# PolIrkutska_DOZATOR_el.net
KiCad netlist of a schematic drawn in EAGLE
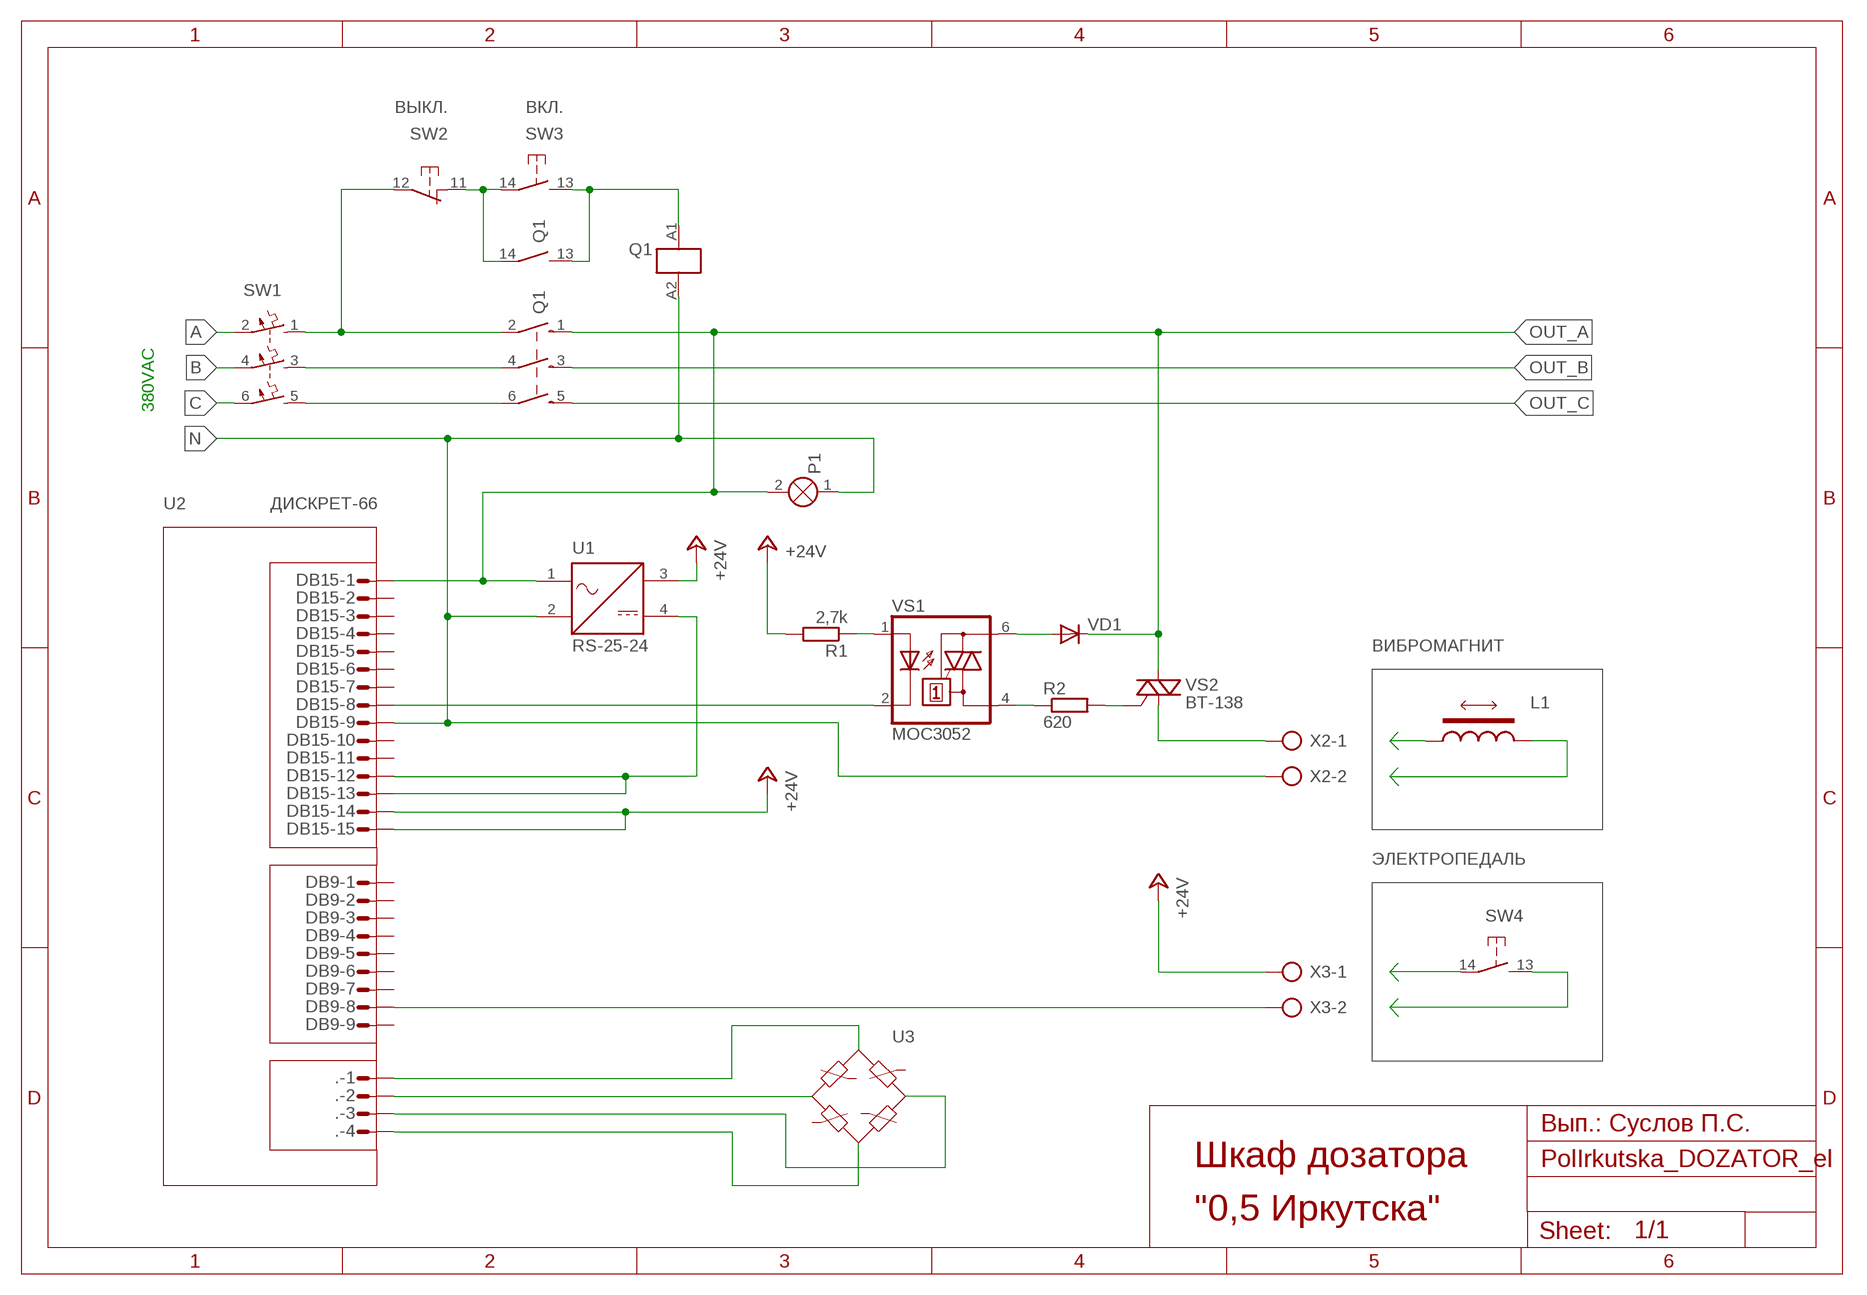
[diagram p0: schematic, sheet 1]

(export (version "E")
  (design (tool "Eeschema 10.0.6"))
  (components
    (comp (ref ".")
      (value "L04P")
      (footprint "eagle-import:L04P")
      (libsource (lib "eagle-import") (part "L04P"))
    )
    (comp (ref "DB9")
      (value "L09P")
      (footprint "eagle-import:L09P")
      (libsource (lib "eagle-import") (part "L09P"))
    )
    (comp (ref "DB15")
      (value "L15P")
      (footprint "eagle-import:L15P")
      (libsource (lib "eagle-import") (part "L15P"))
    )
    (comp (ref "L1")
      (value "L-US0204/5")
      (footprint "eagle-import:0204_5")
      (libsource (lib "eagle-import") (part "L-US0204/5"))
    )
    (comp (ref "P1")
      (value "SIGNALLAMPE")
      (footprint "eagle-import:LAMPE")
      (libsource (lib "eagle-import") (part "SIGNALLAMPE"))
    )
    (comp (ref "Q1")
      (value "HAUPTSCHUETZ_3-POL_HILFSKONTAKT_13-14")
      (footprint "eagle-import:HAUPTSCHUETZ_3-POL+HILFSKONTAKT_13-14")
      (libsource (lib "eagle-import") (part "HAUPTSCHUETZ_3-POL_HILFSKONTAKT_13-14"))
    )
    (comp (ref "R1")
      (value "2,7k")
      (footprint "eagle-import:0204V")
      (libsource (lib "eagle-import") (part "R-EU_0204/2V"))
    )
    (comp (ref "R2")
      (value "620")
      (footprint "eagle-import:0204V")
      (libsource (lib "eagle-import") (part "R-EU_0204/2V"))
    )
    (comp (ref "SW1")
      (value "LEITUNGSSCHUTZSCHALTER_3-POL")
      (footprint "eagle-import:LEITUNGSSCHUTZSCHALTER_3-POL")
      (libsource (lib "eagle-import") (part "LEITUNGSSCHUTZSCHALTER_3-POL"))
    )
    (comp (ref "SW2")
      (value "ВЫКЛ.")
      (footprint "eagle-import:OEFFNER_TASTSCHALTER")
      (libsource (lib "eagle-import") (part "OEFFNER_TASTSCHALTER"))
    )
    (comp (ref "SW3")
      (value "ВКЛ.")
      (footprint "eagle-import:SCHLIESSER_TASTSCHALTER")
      (libsource (lib "eagle-import") (part "SCHLIESSER_TASTSCHALTER"))
    )
    (comp (ref "SW4")
      (value "SCHLIESSER_TASTSCHALTER")
      (footprint "eagle-import:SCHLIESSER_TASTSCHALTER")
      (libsource (lib "eagle-import") (part "SCHLIESSER_TASTSCHALTER"))
    )
    (comp (ref "U1")
      (value "RS-25-24")
      (footprint "eagle-import:NETZTEIL_GLEICHSPANNUNG")
      (libsource (lib "eagle-import") (part "NETZTEIL_GLEICHSPANNUNG"))
    )
    (comp (ref "VD1")
      (value "1N4148DO35-7")
      (footprint "eagle-import:DO35-7")
      (libsource (lib "eagle-import") (part "1N4148DO35-7"))
    )
    (comp (ref "VS1")
      (value "MOC3052")
      (footprint "eagle-import:DIL06B")
      (libsource (lib "eagle-import") (part "MOC30T42"))
    )
    (comp (ref "VS2")
      (value "BT-138")
      (footprint "eagle-import:TRIAC")
      (libsource (lib "eagle-import") (part "TRIAC"))
    )
    (comp (ref "X2")
      (value "AK500/2")
      (footprint "eagle-import:AK500_2")
      (libsource (lib "eagle-import") (part "AK500/2"))
    )
    (comp (ref "X3")
      (value "AK500/2")
      (footprint "eagle-import:AK500_2")
      (libsource (lib "eagle-import") (part "AK500/2"))
    )
  )
  (nets
    (net (code "1") (name "+24V") (class "Default")
      (node (ref "DB15") (pin "14") (pinfunction "S_14") (pintype "passive"))
      (node (ref "DB15") (pin "15") (pinfunction "S_15") (pintype "passive"))
      (node (ref "R1") (pin "2") (pinfunction "2_2") (pintype "passive"))
      (node (ref "U1") (pin "3") (pinfunction "3_3") (pintype "passive"))
      (node (ref "X3") (pin "1") (pinfunction "KL_1") (pintype "passive"))
    )
    (net (code "2") (name "A") (class "Default")
      (node (ref "SW1") (pin "2") (pinfunction "2_2") (pintype "passive"))
    )
    (net (code "3") (name "B") (class "Default")
      (node (ref "SW1") (pin "4") (pinfunction "4_4") (pintype "passive"))
    )
    (net (code "4") (name "C") (class "Default")
      (node (ref "SW1") (pin "6") (pinfunction "6_6") (pintype "passive"))
    )
    (net (code "5") (name "N") (class "Default")
      (node (ref "DB15") (pin "9") (pinfunction "S_9") (pintype "passive"))
      (node (ref "P1") (pin "1") (pinfunction "X1_1") (pintype "passive"))
      (node (ref "Q1") (pin "A2") (pinfunction "A2_A2") (pintype "input"))
      (node (ref "U1") (pin "2") (pinfunction "2_2") (pintype "passive"))
      (node (ref "X2") (pin "2") (pinfunction "KL_2") (pintype "passive"))
    )
    (net (code "6") (name "Net-(DB9H-S)") (class "Default")
      (node (ref "DB9") (pin "8") (pinfunction "S_8") (pintype "passive"))
      (node (ref "X3") (pin "2") (pinfunction "KL_2") (pintype "passive"))
    )
    (net (code "7") (name "Net-(DB15D-S)") (class "Default")
      (node (ref "DB15") (pin "12") (pinfunction "S_12") (pintype "passive"))
      (node (ref "DB15") (pin "13") (pinfunction "S_13") (pintype "passive"))
      (node (ref "U1") (pin "4") (pinfunction "4_4") (pintype "passive"))
    )
    (net (code "8") (name "Net-(DB15N-S)") (class "Default")
      (node (ref "DB15") (pin "8") (pinfunction "S_8") (pintype "passive"))
      (node (ref "VS1") (pin "2") (pinfunction "C_2") (pintype "passive"))
    )
    (net (code "9") (name "Net-(Q1-Pad4)") (class "Default")
      (node (ref "Q1") (pin "4") (pinfunction "4_4") (pintype "passive"))
      (node (ref "SW1") (pin "3") (pinfunction "3_3") (pintype "passive"))
    )
    (net (code "10") (name "Net-(Q1-Pad6)") (class "Default")
      (node (ref "Q1") (pin "6") (pinfunction "6_6") (pintype "passive"))
      (node (ref "SW1") (pin "5") (pinfunction "5_5") (pintype "passive"))
    )
    (net (code "11") (name "Net-(Q1B-3)") (class "Default")
      (node (ref "Q1") (pin "13") (pinfunction "3_13") (pintype "passive"))
      (node (ref "Q1") (pin "A1") (pinfunction "A1_A1") (pintype "input"))
      (node (ref "SW3") (pin "13") (pinfunction "3_13") (pintype "input"))
    )
    (net (code "12") (name "Net-(Q1B-4)") (class "Default")
      (node (ref "Q1") (pin "14") (pinfunction "4_14") (pintype "passive"))
      (node (ref "SW2") (pin "11") (pinfunction "1_11") (pintype "input"))
      (node (ref "SW3") (pin "14") (pinfunction "4_14") (pintype "input"))
    )
    (net (code "13") (name "Net-(R2-Pad2)") (class "Default")
      (node (ref "R2") (pin "2") (pinfunction "2_2") (pintype "passive"))
      (node (ref "VS2") (pin "G") (pinfunction "G_G") (pintype "passive"))
    )
    (net (code "14") (name "Net-(SW2-2)") (class "Default")
      (node (ref "Q1") (pin "2") (pinfunction "2_2") (pintype "passive"))
      (node (ref "SW1") (pin "1") (pinfunction "1_1") (pintype "passive"))
      (node (ref "SW2") (pin "12") (pinfunction "2_12") (pintype "input"))
    )
    (net (code "15") (name "Net-(VS1-A)") (class "Default")
      (node (ref "R1") (pin "1") (pinfunction "1_1") (pintype "passive"))
      (node (ref "VS1") (pin "1") (pinfunction "A_1") (pintype "passive"))
    )
    (net (code "16") (name "Net-(VS1-A1)") (class "Default")
      (node (ref "R2") (pin "1") (pinfunction "1_1") (pintype "passive"))
      (node (ref "VS1") (pin "4") (pinfunction "A1_4") (pintype "passive"))
    )
    (net (code "17") (name "Net-(VS1-A2)") (class "Default")
      (node (ref "VD1") (pin "A") (pinfunction "A_A") (pintype "passive"))
      (node (ref "VS1") (pin "6") (pinfunction "A2_6") (pintype "passive"))
    )
    (net (code "18") (name "Net-(X2A-KL)") (class "Default")
      (node (ref "VS2") (pin "A2") (pinfunction "A2_A2") (pintype "passive"))
      (node (ref "X2") (pin "1") (pinfunction "KL_1") (pintype "passive"))
    )
    (net (code "19") (name "OUT_A") (class "Default")
      (node (ref "DB15") (pin "1") (pinfunction "S_1") (pintype "passive"))
      (node (ref "P1") (pin "2") (pinfunction "X2_2") (pintype "passive"))
      (node (ref "Q1") (pin "1") (pinfunction "1_1") (pintype "passive"))
      (node (ref "U1") (pin "1") (pinfunction "1_1") (pintype "passive"))
      (node (ref "VD1") (pin "C") (pinfunction "C_C") (pintype "passive"))
      (node (ref "VS2") (pin "A1") (pinfunction "A1_A1") (pintype "passive"))
    )
    (net (code "20") (name "OUT_B") (class "Default")
      (node (ref "Q1") (pin "3") (pinfunction "3_3") (pintype "passive"))
    )
    (net (code "21") (name "OUT_C") (class "Default")
      (node (ref "Q1") (pin "5") (pinfunction "5_5") (pintype "passive"))
    )
    (net (code "22") (name "unconnected-(.A-S-Pad1)") (class "Default")
      (node (ref ".") (pin "1") (pinfunction "S_1") (pintype "passive"))
    )
    (net (code "23") (name "unconnected-(.B-S-Pad2)") (class "Default")
      (node (ref ".") (pin "2") (pinfunction "S_2") (pintype "passive"))
    )
    (net (code "24") (name "unconnected-(.C-S-Pad3)") (class "Default")
      (node (ref ".") (pin "3") (pinfunction "S_3") (pintype "passive"))
    )
    (net (code "25") (name "unconnected-(.D-S-Pad4)") (class "Default")
      (node (ref ".") (pin "4") (pinfunction "S_4") (pintype "passive"))
    )
    (net (code "26") (name "unconnected-(DB9A-S-Pad1)") (class "Default")
      (node (ref "DB9") (pin "1") (pinfunction "S_1") (pintype "passive"))
    )
    (net (code "27") (name "unconnected-(DB9B-S-Pad2)") (class "Default")
      (node (ref "DB9") (pin "2") (pinfunction "S_2") (pintype "passive"))
    )
    (net (code "28") (name "unconnected-(DB9C-S-Pad3)") (class "Default")
      (node (ref "DB9") (pin "3") (pinfunction "S_3") (pintype "passive"))
    )
    (net (code "29") (name "unconnected-(DB9D-S-Pad4)") (class "Default")
      (node (ref "DB9") (pin "4") (pinfunction "S_4") (pintype "passive"))
    )
    (net (code "30") (name "unconnected-(DB9E-S-Pad5)") (class "Default")
      (node (ref "DB9") (pin "5") (pinfunction "S_5") (pintype "passive"))
    )
    (net (code "31") (name "unconnected-(DB9F-S-Pad6)") (class "Default")
      (node (ref "DB9") (pin "6") (pinfunction "S_6") (pintype "passive"))
    )
    (net (code "32") (name "unconnected-(DB9G-S-Pad7)") (class "Default")
      (node (ref "DB9") (pin "7") (pinfunction "S_7") (pintype "passive"))
    )
    (net (code "33") (name "unconnected-(DB9I-S-Pad9)") (class "Default")
      (node (ref "DB9") (pin "9") (pinfunction "S_9") (pintype "passive"))
    )
    (net (code "34") (name "unconnected-(DB15B-S-Pad10)") (class "Default")
      (node (ref "DB15") (pin "10") (pinfunction "S_10") (pintype "passive"))
    )
    (net (code "35") (name "unconnected-(DB15C-S-Pad11)") (class "Default")
      (node (ref "DB15") (pin "11") (pinfunction "S_11") (pintype "passive"))
    )
    (net (code "36") (name "unconnected-(DB15H-S-Pad2)") (class "Default")
      (node (ref "DB15") (pin "2") (pinfunction "S_2") (pintype "passive"))
    )
    (net (code "37") (name "unconnected-(DB15I-S-Pad3)") (class "Default")
      (node (ref "DB15") (pin "3") (pinfunction "S_3") (pintype "passive"))
    )
    (net (code "38") (name "unconnected-(DB15J-S-Pad4)") (class "Default")
      (node (ref "DB15") (pin "4") (pinfunction "S_4") (pintype "passive"))
    )
    (net (code "39") (name "unconnected-(DB15K-S-Pad5)") (class "Default")
      (node (ref "DB15") (pin "5") (pinfunction "S_5") (pintype "passive"))
    )
    (net (code "40") (name "unconnected-(DB15L-S-Pad6)") (class "Default")
      (node (ref "DB15") (pin "6") (pinfunction "S_6") (pintype "passive"))
    )
    (net (code "41") (name "unconnected-(DB15M-S-Pad7)") (class "Default")
      (node (ref "DB15") (pin "7") (pinfunction "S_7") (pintype "passive"))
    )
    (net (code "42") (name "unconnected-(L1-Pad1)") (class "Default")
      (node (ref "L1") (pin "1") (pinfunction "1_1") (pintype "passive"))
    )
    (net (code "43") (name "unconnected-(L1-Pad2)") (class "Default")
      (node (ref "L1") (pin "2") (pinfunction "2_2") (pintype "passive"))
    )
    (net (code "44") (name "unconnected-(SW4-3-Pad13)") (class "Default")
      (node (ref "SW4") (pin "13") (pinfunction "3_13") (pintype "input"))
    )
    (net (code "45") (name "unconnected-(SW4-4-Pad14)") (class "Default")
      (node (ref "SW4") (pin "14") (pinfunction "4_14") (pintype "input"))
    )
  )
)
